# ATEM_2x8GPIOv1_1.net
KiCad netlist of a schematic drawn in EAGLE
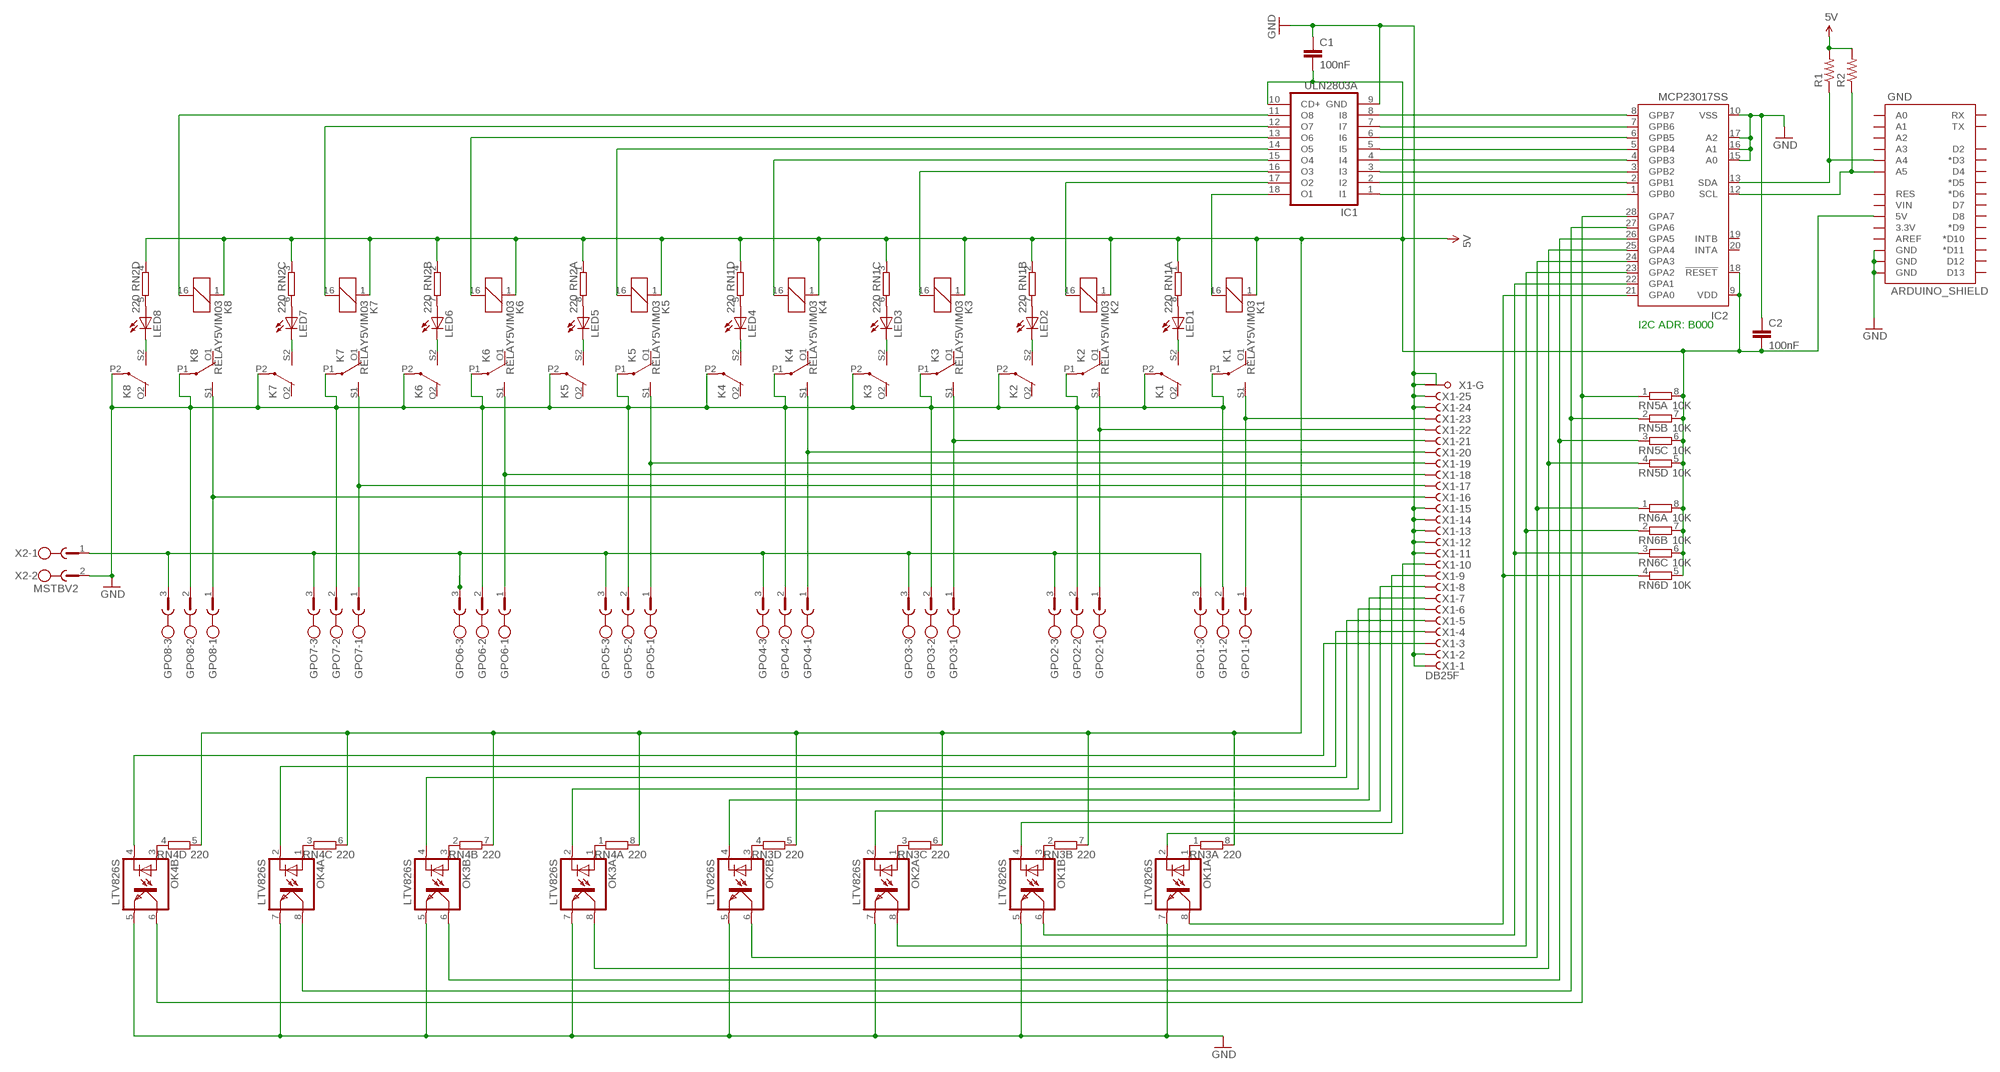
[diagram p0: schematic, sheet 1]

(export (version "E")
  (design (tool "Eeschema 10.0.6"))
  (components
    (comp (ref "C1")
      (value "100nF")
      (footprint "eagle-import:0805")
      (libsource (lib "eagle-import") (part "CAP0805"))
    )
    (comp (ref "C2")
      (value "100nF")
      (footprint "eagle-import:0603-CAP")
      (libsource (lib "eagle-import") (part "CAP0603-CAP"))
    )
    (comp (ref "GND")
      (value "ARDUINO_SHIELD")
      (footprint "eagle-import:ARDUINO_BOXSHIELD_NOHOLES")
      (libsource (lib "eagle-import") (part "ARDUINO_SHIELD"))
    )
    (comp (ref "GPO1")
      (value "CON1")
      (footprint "eagle-import:MSTBV3")
      (fields (field (name "MPN") "MSTBV 2,5/3-GF-5.08"))
      (libsource (lib "eagle-import") (part "MSTBV3"))
    )
    (comp (ref "GPO2")
      (value "CON1")
      (footprint "eagle-import:MSTBV3")
      (fields (field (name "MPN") "MSTBV 2,5/3-GF-5.08"))
      (libsource (lib "eagle-import") (part "MSTBV3"))
    )
    (comp (ref "GPO3")
      (value "CON1")
      (footprint "eagle-import:MSTBV3")
      (fields (field (name "MPN") "MSTBV 2,5/3-GF-5.08"))
      (libsource (lib "eagle-import") (part "MSTBV3"))
    )
    (comp (ref "GPO4")
      (value "CON1")
      (footprint "eagle-import:MSTBV3")
      (fields (field (name "MPN") "MSTBV 2,5/3-GF-5.08"))
      (libsource (lib "eagle-import") (part "MSTBV3"))
    )
    (comp (ref "GPO5")
      (value "CON1")
      (footprint "eagle-import:MSTBV3")
      (fields (field (name "MPN") "MSTBV 2,5/3-GF-5.08"))
      (libsource (lib "eagle-import") (part "MSTBV3"))
    )
    (comp (ref "GPO6")
      (value "CON1")
      (footprint "eagle-import:MSTBV3")
      (fields (field (name "MPN") "MSTBV 2,5/3-GF-5.08"))
      (libsource (lib "eagle-import") (part "MSTBV3"))
    )
    (comp (ref "GPO7")
      (value "CON1")
      (footprint "eagle-import:MSTBV3")
      (fields (field (name "MPN") "MSTBV 2,5/3-GF-5.08"))
      (libsource (lib "eagle-import") (part "MSTBV3"))
    )
    (comp (ref "GPO8")
      (value "GPO8")
      (footprint "eagle-import:MSTBV3")
      (fields (field (name "MPN") "MSTBV 2,5/3-GF-5.08"))
      (libsource (lib "eagle-import") (part "MSTBV3"))
    )
    (comp (ref "IC1")
      (value "ULN2803A")
      (footprint "eagle-import:SO18W")
      (libsource (lib "eagle-import") (part "ULN2803ASO18W"))
    )
    (comp (ref "IC2")
      (value "MCP23017SS")
      (footprint "eagle-import:SSOP28")
      (fields (field (name "MF") "MICROCHIP") (field (name "MPN") "MCP23017-E/SS"))
      (libsource (lib "eagle-import") (part "MCP23017SS"))
    )
    (comp (ref "K1")
      (value "RELAY5VIM03")
      (footprint "eagle-import:DS2Y")
      (libsource (lib "eagle-import") (part "RELAY5VIM03"))
    )
    (comp (ref "K2")
      (value "RELAY5VIM03")
      (footprint "eagle-import:DS2Y")
      (libsource (lib "eagle-import") (part "RELAY5VIM03"))
    )
    (comp (ref "K3")
      (value "RELAY5VIM03")
      (footprint "eagle-import:DS2Y")
      (libsource (lib "eagle-import") (part "RELAY5VIM03"))
    )
    (comp (ref "K4")
      (value "RELAY5VIM03")
      (footprint "eagle-import:DS2Y")
      (libsource (lib "eagle-import") (part "RELAY5VIM03"))
    )
    (comp (ref "K5")
      (value "RELAY5VIM03")
      (footprint "eagle-import:DS2Y")
      (libsource (lib "eagle-import") (part "RELAY5VIM03"))
    )
    (comp (ref "K6")
      (value "RELAY5VIM03")
      (footprint "eagle-import:DS2Y")
      (libsource (lib "eagle-import") (part "RELAY5VIM03"))
    )
    (comp (ref "K7")
      (value "RELAY5VIM03")
      (footprint "eagle-import:DS2Y")
      (libsource (lib "eagle-import") (part "RELAY5VIM03"))
    )
    (comp (ref "K8")
      (value "RELAY5VIM03")
      (footprint "eagle-import:DS2Y")
      (libsource (lib "eagle-import") (part "RELAY5VIM03"))
    )
    (comp (ref "LED1")
      (value "LED0603")
      (footprint "eagle-import:LED-0603")
      (libsource (lib "eagle-import") (part "LED0603"))
    )
    (comp (ref "LED2")
      (value "LED0603")
      (footprint "eagle-import:LED-0603")
      (libsource (lib "eagle-import") (part "LED0603"))
    )
    (comp (ref "LED3")
      (value "LED0603")
      (footprint "eagle-import:LED-0603")
      (libsource (lib "eagle-import") (part "LED0603"))
    )
    (comp (ref "LED4")
      (value "LED0603")
      (footprint "eagle-import:LED-0603")
      (libsource (lib "eagle-import") (part "LED0603"))
    )
    (comp (ref "LED5")
      (value "LED0603")
      (footprint "eagle-import:LED-0603")
      (libsource (lib "eagle-import") (part "LED0603"))
    )
    (comp (ref "LED6")
      (value "LED0603")
      (footprint "eagle-import:LED-0603")
      (libsource (lib "eagle-import") (part "LED0603"))
    )
    (comp (ref "LED7")
      (value "LED0603")
      (footprint "eagle-import:LED-0603")
      (libsource (lib "eagle-import") (part "LED0603"))
    )
    (comp (ref "LED8")
      (value "LED0603")
      (footprint "eagle-import:LED-0603")
      (libsource (lib "eagle-import") (part "LED0603"))
    )
    (comp (ref "OK1")
      (value "LTV826S")
      (footprint "eagle-import:DIL8-SMD")
      (libsource (lib "eagle-import") (part "LTV826S"))
    )
    (comp (ref "OK2")
      (value "LTV826S")
      (footprint "eagle-import:DIL8-SMD")
      (libsource (lib "eagle-import") (part "LTV826S"))
    )
    (comp (ref "OK3")
      (value "LTV826S")
      (footprint "eagle-import:DIL8-SMD")
      (libsource (lib "eagle-import") (part "LTV826S"))
    )
    (comp (ref "OK4")
      (value "LTV826S")
      (footprint "eagle-import:DIL8-SMD")
      (libsource (lib "eagle-import") (part "LTV826S"))
    )
    (comp (ref "R1")
      (value "RESISTOR0603-RES")
      (footprint "eagle-import:0603-RES")
      (libsource (lib "eagle-import") (part "RESISTOR0603-RES"))
    )
    (comp (ref "R2")
      (value "RESISTOR0603-RES")
      (footprint "eagle-import:0603-RES")
      (libsource (lib "eagle-import") (part "RESISTOR0603-RES"))
    )
    (comp (ref "RN1")
      (value "220")
      (footprint "eagle-import:CAY16")
      (libsource (lib "eagle-import") (part "4R-NCAY16"))
    )
    (comp (ref "RN2")
      (value "220")
      (footprint "eagle-import:CAY16")
      (libsource (lib "eagle-import") (part "4R-NCAY16"))
    )
    (comp (ref "RN3")
      (value "220")
      (footprint "eagle-import:CAY16")
      (libsource (lib "eagle-import") (part "4R-NCAY16"))
    )
    (comp (ref "RN4")
      (value "220")
      (footprint "eagle-import:CAY16")
      (libsource (lib "eagle-import") (part "4R-NCAY16"))
    )
    (comp (ref "RN5")
      (value "10K")
      (footprint "eagle-import:CAY16")
      (libsource (lib "eagle-import") (part "4R-NCAY16"))
    )
    (comp (ref "RN6")
      (value "10K")
      (footprint "eagle-import:CAY16")
      (libsource (lib "eagle-import") (part "4R-NCAY16"))
    )
    (comp (ref "X1")
      (value "DB25F")
      (footprint "eagle-import:F25HP")
      (libsource (lib "eagle-import") (part "F25HPS"))
    )
    (comp (ref "X2")
      (value "MSTBV2")
      (footprint "eagle-import:MSTBV2")
      (fields (field (name "MPN") "MSTBV 2,5/2-GF-5.08"))
      (libsource (lib "eagle-import") (part "MSTBV2"))
    )
  )
  (nets
    (net (code "1") (name "5V") (class "Default")
      (node (ref "C1") (pin "2") (pinfunction "2_2") (pintype "passive"))
      (node (ref "C2") (pin "2") (pinfunction "2_2") (pintype "passive"))
      (node (ref "GND") (pin "5V@0") (pinfunction "5V_5V@0") (pintype "bidirectional"))
      (node (ref "IC1") (pin "10") (pinfunction "CD+_10") (pintype "passive"))
      (node (ref "IC2") (pin "18") (pinfunction "~{RESET}_18") (pintype "input"))
      (node (ref "IC2") (pin "9") (pinfunction "VDD_9") (pintype "power_in"))
      (node (ref "K1") (pin "1") (pinfunction "1_1") (pintype "passive"))
      (node (ref "K2") (pin "1") (pinfunction "1_1") (pintype "passive"))
      (node (ref "K3") (pin "1") (pinfunction "1_1") (pintype "passive"))
      (node (ref "K4") (pin "1") (pinfunction "1_1") (pintype "passive"))
      (node (ref "K5") (pin "1") (pinfunction "1_1") (pintype "passive"))
      (node (ref "K6") (pin "1") (pinfunction "1_1") (pintype "passive"))
      (node (ref "K7") (pin "1") (pinfunction "1_1") (pintype "passive"))
      (node (ref "K8") (pin "1") (pinfunction "1_1") (pintype "passive"))
      (node (ref "R1") (pin "2") (pinfunction "2_2") (pintype "passive"))
      (node (ref "R2") (pin "2") (pinfunction "2_2") (pintype "passive"))
      (node (ref "RN1") (pin "1") (pinfunction "1_1") (pintype "passive"))
      (node (ref "RN1") (pin "2") (pinfunction "1_2") (pintype "passive"))
      (node (ref "RN1") (pin "3") (pinfunction "1_3") (pintype "passive"))
      (node (ref "RN1") (pin "4") (pinfunction "1_4") (pintype "passive"))
      (node (ref "RN2") (pin "1") (pinfunction "1_1") (pintype "passive"))
      (node (ref "RN2") (pin "2") (pinfunction "1_2") (pintype "passive"))
      (node (ref "RN2") (pin "3") (pinfunction "1_3") (pintype "passive"))
      (node (ref "RN2") (pin "4") (pinfunction "1_4") (pintype "passive"))
      (node (ref "RN3") (pin "5") (pinfunction "2_5") (pintype "passive"))
      (node (ref "RN3") (pin "6") (pinfunction "2_6") (pintype "passive"))
      (node (ref "RN3") (pin "7") (pinfunction "2_7") (pintype "passive"))
      (node (ref "RN3") (pin "8") (pinfunction "2_8") (pintype "passive"))
      (node (ref "RN4") (pin "5") (pinfunction "2_5") (pintype "passive"))
      (node (ref "RN4") (pin "6") (pinfunction "2_6") (pintype "passive"))
      (node (ref "RN4") (pin "7") (pinfunction "2_7") (pintype "passive"))
      (node (ref "RN4") (pin "8") (pinfunction "2_8") (pintype "passive"))
      (node (ref "RN5") (pin "5") (pinfunction "2_5") (pintype "passive"))
      (node (ref "RN5") (pin "6") (pinfunction "2_6") (pintype "passive"))
      (node (ref "RN5") (pin "7") (pinfunction "2_7") (pintype "passive"))
      (node (ref "RN5") (pin "8") (pinfunction "2_8") (pintype "passive"))
      (node (ref "RN6") (pin "5") (pinfunction "2_5") (pintype "passive"))
      (node (ref "RN6") (pin "6") (pinfunction "2_6") (pintype "passive"))
      (node (ref "RN6") (pin "7") (pinfunction "2_7") (pintype "passive"))
      (node (ref "RN6") (pin "8") (pinfunction "2_8") (pintype "passive"))
    )
    (net (code "2") (name "GND") (class "Default")
      (node (ref "C1") (pin "1") (pinfunction "1_1") (pintype "passive"))
      (node (ref "C2") (pin "1") (pinfunction "1_1") (pintype "passive"))
      (node (ref "GND") (pin "GND@0") (pinfunction "GND_GND@0") (pintype "bidirectional"))
      (node (ref "GND") (pin "GND@1") (pinfunction "GND_GND@1") (pintype "bidirectional"))
      (node (ref "GND") (pin "GND@4") (pinfunction "GND_GND@4") (pintype "bidirectional"))
      (node (ref "GPO1") (pin "2") (pinfunction "1_2") (pintype "passive"))
      (node (ref "GPO2") (pin "2") (pinfunction "1_2") (pintype "passive"))
      (node (ref "GPO3") (pin "2") (pinfunction "1_2") (pintype "passive"))
      (node (ref "GPO4") (pin "2") (pinfunction "1_2") (pintype "passive"))
      (node (ref "GPO5") (pin "2") (pinfunction "1_2") (pintype "passive"))
      (node (ref "GPO6") (pin "2") (pinfunction "1_2") (pintype "passive"))
      (node (ref "GPO7") (pin "2") (pinfunction "1_2") (pintype "passive"))
      (node (ref "GPO8") (pin "2") (pinfunction "1_2") (pintype "passive"))
      (node (ref "IC1") (pin "9") (pinfunction "GND_9") (pintype "power_in"))
      (node (ref "IC2") (pin "10") (pinfunction "VSS_10") (pintype "power_in"))
      (node (ref "IC2") (pin "15") (pinfunction "A0_15") (pintype "input"))
      (node (ref "IC2") (pin "16") (pinfunction "A1_16") (pintype "input"))
      (node (ref "IC2") (pin "17") (pinfunction "A2_17") (pintype "input"))
      (node (ref "K1") (pin "P1") (pinfunction "P_P1") (pintype "passive"))
      (node (ref "K1") (pin "P2") (pinfunction "P_P2") (pintype "passive"))
      (node (ref "K2") (pin "P1") (pinfunction "P_P1") (pintype "passive"))
      (node (ref "K2") (pin "P2") (pinfunction "P_P2") (pintype "passive"))
      (node (ref "K3") (pin "P1") (pinfunction "P_P1") (pintype "passive"))
      (node (ref "K3") (pin "P2") (pinfunction "P_P2") (pintype "passive"))
      (node (ref "K4") (pin "P1") (pinfunction "P_P1") (pintype "passive"))
      (node (ref "K4") (pin "P2") (pinfunction "P_P2") (pintype "passive"))
      (node (ref "K5") (pin "P1") (pinfunction "P_P1") (pintype "passive"))
      (node (ref "K5") (pin "P2") (pinfunction "P_P2") (pintype "passive"))
      (node (ref "K6") (pin "P1") (pinfunction "P_P1") (pintype "passive"))
      (node (ref "K6") (pin "P2") (pinfunction "P_P2") (pintype "passive"))
      (node (ref "K7") (pin "P1") (pinfunction "P_P1") (pintype "passive"))
      (node (ref "K7") (pin "P2") (pinfunction "P_P2") (pintype "passive"))
      (node (ref "K8") (pin "P1") (pinfunction "P_P1") (pintype "passive"))
      (node (ref "K8") (pin "P2") (pinfunction "P_P2") (pintype "passive"))
      (node (ref "OK1") (pin "5") (pinfunction "EMIT_5") (pintype "passive"))
      (node (ref "OK1") (pin "7") (pinfunction "EMIT_7") (pintype "passive"))
      (node (ref "OK2") (pin "5") (pinfunction "EMIT_5") (pintype "passive"))
      (node (ref "OK2") (pin "7") (pinfunction "EMIT_7") (pintype "passive"))
      (node (ref "OK3") (pin "5") (pinfunction "EMIT_5") (pintype "passive"))
      (node (ref "OK3") (pin "7") (pinfunction "EMIT_7") (pintype "passive"))
      (node (ref "OK4") (pin "5") (pinfunction "EMIT_5") (pintype "passive"))
      (node (ref "OK4") (pin "7") (pinfunction "EMIT_7") (pintype "passive"))
      (node (ref "X1") (pin "1") (pinfunction "F_1") (pintype "passive"))
      (node (ref "X1") (pin "11") (pinfunction "F_11") (pintype "passive"))
      (node (ref "X1") (pin "12") (pinfunction "F_12") (pintype "passive"))
      (node (ref "X1") (pin "13") (pinfunction "F_13") (pintype "passive"))
      (node (ref "X1") (pin "14") (pinfunction "F_14") (pintype "passive"))
      (node (ref "X1") (pin "15") (pinfunction "F_15") (pintype "passive"))
      (node (ref "X1") (pin "2") (pinfunction "F_2") (pintype "passive"))
      (node (ref "X1") (pin "24") (pinfunction "F_24") (pintype "passive"))
      (node (ref "X1") (pin "25") (pinfunction "F_25") (pintype "passive"))
      (node (ref "X1") (pin "G1") (pinfunction "G1_G1") (pintype "passive"))
      (node (ref "X1") (pin "G2") (pinfunction "G2_G2") (pintype "passive"))
      (node (ref "X2") (pin "2") (pinfunction "1_2") (pintype "passive"))
    )
    (net (code "3") (name "Net-(GPO1C-1)") (class "Default")
      (node (ref "GPO1") (pin "3") (pinfunction "1_3") (pintype "passive"))
      (node (ref "GPO2") (pin "3") (pinfunction "1_3") (pintype "passive"))
      (node (ref "GPO3") (pin "3") (pinfunction "1_3") (pintype "passive"))
      (node (ref "GPO4") (pin "3") (pinfunction "1_3") (pintype "passive"))
      (node (ref "GPO5") (pin "3") (pinfunction "1_3") (pintype "passive"))
      (node (ref "GPO6") (pin "3") (pinfunction "1_3") (pintype "passive"))
      (node (ref "GPO7") (pin "3") (pinfunction "1_3") (pintype "passive"))
      (node (ref "GPO8") (pin "3") (pinfunction "1_3") (pintype "passive"))
      (node (ref "X2") (pin "1") (pinfunction "1_1") (pintype "passive"))
    )
    (net (code "4") (name "Net-(IC1-I1)") (class "Default")
      (node (ref "IC1") (pin "1") (pinfunction "I1_1") (pintype "input"))
      (node (ref "IC2") (pin "1") (pinfunction "GPB0_1") (pintype "bidirectional"))
    )
    (net (code "5") (name "Net-(IC1-I2)") (class "Default")
      (node (ref "IC1") (pin "2") (pinfunction "I2_2") (pintype "input"))
      (node (ref "IC2") (pin "2") (pinfunction "GPB1_2") (pintype "bidirectional"))
    )
    (net (code "6") (name "Net-(IC1-I3)") (class "Default")
      (node (ref "IC1") (pin "3") (pinfunction "I3_3") (pintype "input"))
      (node (ref "IC2") (pin "3") (pinfunction "GPB2_3") (pintype "bidirectional"))
    )
    (net (code "7") (name "Net-(IC1-I4)") (class "Default")
      (node (ref "IC1") (pin "4") (pinfunction "I4_4") (pintype "input"))
      (node (ref "IC2") (pin "4") (pinfunction "GPB3_4") (pintype "bidirectional"))
    )
    (net (code "8") (name "Net-(IC1-I5)") (class "Default")
      (node (ref "IC1") (pin "5") (pinfunction "I5_5") (pintype "input"))
      (node (ref "IC2") (pin "5") (pinfunction "GPB4_5") (pintype "bidirectional"))
    )
    (net (code "9") (name "Net-(IC1-I6)") (class "Default")
      (node (ref "IC1") (pin "6") (pinfunction "I6_6") (pintype "input"))
      (node (ref "IC2") (pin "6") (pinfunction "GPB5_6") (pintype "bidirectional"))
    )
    (net (code "10") (name "Net-(IC1-I7)") (class "Default")
      (node (ref "IC1") (pin "7") (pinfunction "I7_7") (pintype "input"))
      (node (ref "IC2") (pin "7") (pinfunction "GPB6_7") (pintype "bidirectional"))
    )
    (net (code "11") (name "Net-(IC1-I8)") (class "Default")
      (node (ref "IC1") (pin "8") (pinfunction "I8_8") (pintype "input"))
      (node (ref "IC2") (pin "8") (pinfunction "GPB7_8") (pintype "bidirectional"))
    )
    (net (code "12") (name "Net-(IC1-O1)") (class "Default")
      (node (ref "IC1") (pin "18") (pinfunction "O1_18") (pintype "open_collector"))
      (node (ref "K1") (pin "16") (pinfunction "2_16") (pintype "passive"))
    )
    (net (code "13") (name "Net-(IC1-O2)") (class "Default")
      (node (ref "IC1") (pin "17") (pinfunction "O2_17") (pintype "open_collector"))
      (node (ref "K2") (pin "16") (pinfunction "2_16") (pintype "passive"))
    )
    (net (code "14") (name "Net-(IC1-O3)") (class "Default")
      (node (ref "IC1") (pin "16") (pinfunction "O3_16") (pintype "open_collector"))
      (node (ref "K3") (pin "16") (pinfunction "2_16") (pintype "passive"))
    )
    (net (code "15") (name "Net-(IC1-O4)") (class "Default")
      (node (ref "IC1") (pin "15") (pinfunction "O4_15") (pintype "open_collector"))
      (node (ref "K4") (pin "16") (pinfunction "2_16") (pintype "passive"))
    )
    (net (code "16") (name "Net-(IC1-O5)") (class "Default")
      (node (ref "IC1") (pin "14") (pinfunction "O5_14") (pintype "open_collector"))
      (node (ref "K5") (pin "16") (pinfunction "2_16") (pintype "passive"))
    )
    (net (code "17") (name "Net-(IC1-O6)") (class "Default")
      (node (ref "IC1") (pin "13") (pinfunction "O6_13") (pintype "open_collector"))
      (node (ref "K6") (pin "16") (pinfunction "2_16") (pintype "passive"))
    )
    (net (code "18") (name "Net-(IC1-O7)") (class "Default")
      (node (ref "IC1") (pin "12") (pinfunction "O7_12") (pintype "open_collector"))
      (node (ref "K7") (pin "16") (pinfunction "2_16") (pintype "passive"))
    )
    (net (code "19") (name "Net-(IC1-O8)") (class "Default")
      (node (ref "IC1") (pin "11") (pinfunction "O8_11") (pintype "open_collector"))
      (node (ref "K8") (pin "16") (pinfunction "2_16") (pintype "passive"))
    )
    (net (code "20") (name "Net-(IC2-GPA0)") (class "Default")
      (node (ref "IC2") (pin "21") (pinfunction "GPA0_21") (pintype "bidirectional"))
      (node (ref "OK1") (pin "8") (pinfunction "COL_8") (pintype "passive"))
      (node (ref "RN6") (pin "4") (pinfunction "1_4") (pintype "passive"))
    )
    (net (code "21") (name "Net-(IC2-GPA1)") (class "Default")
      (node (ref "IC2") (pin "22") (pinfunction "GPA1_22") (pintype "bidirectional"))
      (node (ref "OK1") (pin "6") (pinfunction "COL_6") (pintype "passive"))
      (node (ref "RN6") (pin "3") (pinfunction "1_3") (pintype "passive"))
    )
    (net (code "22") (name "Net-(IC2-GPA2)") (class "Default")
      (node (ref "IC2") (pin "23") (pinfunction "GPA2_23") (pintype "bidirectional"))
      (node (ref "OK2") (pin "8") (pinfunction "COL_8") (pintype "passive"))
      (node (ref "RN6") (pin "2") (pinfunction "1_2") (pintype "passive"))
    )
    (net (code "23") (name "Net-(IC2-GPA3)") (class "Default")
      (node (ref "IC2") (pin "24") (pinfunction "GPA3_24") (pintype "bidirectional"))
      (node (ref "OK2") (pin "6") (pinfunction "COL_6") (pintype "passive"))
      (node (ref "RN6") (pin "1") (pinfunction "1_1") (pintype "passive"))
    )
    (net (code "24") (name "Net-(IC2-GPA4)") (class "Default")
      (node (ref "IC2") (pin "25") (pinfunction "GPA4_25") (pintype "bidirectional"))
      (node (ref "OK3") (pin "8") (pinfunction "COL_8") (pintype "passive"))
      (node (ref "RN5") (pin "4") (pinfunction "1_4") (pintype "passive"))
    )
    (net (code "25") (name "Net-(IC2-GPA5)") (class "Default")
      (node (ref "IC2") (pin "26") (pinfunction "GPA5_26") (pintype "bidirectional"))
      (node (ref "OK3") (pin "6") (pinfunction "COL_6") (pintype "passive"))
      (node (ref "RN5") (pin "3") (pinfunction "1_3") (pintype "passive"))
    )
    (net (code "26") (name "Net-(IC2-GPA6)") (class "Default")
      (node (ref "IC2") (pin "27") (pinfunction "GPA6_27") (pintype "bidirectional"))
      (node (ref "OK4") (pin "8") (pinfunction "COL_8") (pintype "passive"))
      (node (ref "RN5") (pin "2") (pinfunction "1_2") (pintype "passive"))
    )
    (net (code "27") (name "Net-(IC2-GPA7)") (class "Default")
      (node (ref "IC2") (pin "28") (pinfunction "GPA7_28") (pintype "bidirectional"))
      (node (ref "OK4") (pin "6") (pinfunction "COL_6") (pintype "passive"))
      (node (ref "RN5") (pin "1") (pinfunction "1_1") (pintype "passive"))
    )
    (net (code "28") (name "Net-(IC2-SCL)") (class "Default")
      (node (ref "GND") (pin "A5") (pinfunction "A5_A5") (pintype "bidirectional"))
      (node (ref "IC2") (pin "12") (pinfunction "SCL_12") (pintype "input"))
      (node (ref "R2") (pin "1") (pinfunction "1_1") (pintype "passive"))
    )
    (net (code "29") (name "Net-(IC2-SDA)") (class "Default")
      (node (ref "GND") (pin "A4") (pinfunction "A4_A4") (pintype "bidirectional"))
      (node (ref "IC2") (pin "13") (pinfunction "SDA_13") (pintype "bidirectional"))
      (node (ref "R1") (pin "1") (pinfunction "1_1") (pintype "passive"))
    )
    (net (code "30") (name "Net-(K1B-S)") (class "Default")
      (node (ref "GPO1") (pin "1") (pinfunction "1_1") (pintype "passive"))
      (node (ref "K1") (pin "S1") (pinfunction "S_S1") (pintype "passive"))
      (node (ref "X1") (pin "23") (pinfunction "F_23") (pintype "passive"))
    )
    (net (code "31") (name "Net-(K1C-S)") (class "Default")
      (node (ref "K1") (pin "S2") (pinfunction "S_S2") (pintype "passive"))
      (node (ref "LED1") (pin "C") (pinfunction "C_C") (pintype "passive"))
    )
    (net (code "32") (name "Net-(K2B-S)") (class "Default")
      (node (ref "GPO2") (pin "1") (pinfunction "1_1") (pintype "passive"))
      (node (ref "K2") (pin "S1") (pinfunction "S_S1") (pintype "passive"))
      (node (ref "X1") (pin "22") (pinfunction "F_22") (pintype "passive"))
    )
    (net (code "33") (name "Net-(K2C-S)") (class "Default")
      (node (ref "K2") (pin "S2") (pinfunction "S_S2") (pintype "passive"))
      (node (ref "LED2") (pin "C") (pinfunction "C_C") (pintype "passive"))
    )
    (net (code "34") (name "Net-(K3B-S)") (class "Default")
      (node (ref "GPO3") (pin "1") (pinfunction "1_1") (pintype "passive"))
      (node (ref "K3") (pin "S1") (pinfunction "S_S1") (pintype "passive"))
      (node (ref "X1") (pin "21") (pinfunction "F_21") (pintype "passive"))
    )
    (net (code "35") (name "Net-(K3C-S)") (class "Default")
      (node (ref "K3") (pin "S2") (pinfunction "S_S2") (pintype "passive"))
      (node (ref "LED3") (pin "C") (pinfunction "C_C") (pintype "passive"))
    )
    (net (code "36") (name "Net-(K4B-S)") (class "Default")
      (node (ref "GPO4") (pin "1") (pinfunction "1_1") (pintype "passive"))
      (node (ref "K4") (pin "S1") (pinfunction "S_S1") (pintype "passive"))
      (node (ref "X1") (pin "20") (pinfunction "F_20") (pintype "passive"))
    )
    (net (code "37") (name "Net-(K4C-S)") (class "Default")
      (node (ref "K4") (pin "S2") (pinfunction "S_S2") (pintype "passive"))
      (node (ref "LED4") (pin "C") (pinfunction "C_C") (pintype "passive"))
    )
    (net (code "38") (name "Net-(K5B-S)") (class "Default")
      (node (ref "GPO5") (pin "1") (pinfunction "1_1") (pintype "passive"))
      (node (ref "K5") (pin "S1") (pinfunction "S_S1") (pintype "passive"))
      (node (ref "X1") (pin "19") (pinfunction "F_19") (pintype "passive"))
    )
    (net (code "39") (name "Net-(K5C-S)") (class "Default")
      (node (ref "K5") (pin "S2") (pinfunction "S_S2") (pintype "passive"))
      (node (ref "LED5") (pin "C") (pinfunction "C_C") (pintype "passive"))
    )
    (net (code "40") (name "Net-(K6B-S)") (class "Default")
      (node (ref "GPO6") (pin "1") (pinfunction "1_1") (pintype "passive"))
      (node (ref "K6") (pin "S1") (pinfunction "S_S1") (pintype "passive"))
      (node (ref "X1") (pin "18") (pinfunction "F_18") (pintype "passive"))
    )
    (net (code "41") (name "Net-(K6C-S)") (class "Default")
      (node (ref "K6") (pin "S2") (pinfunction "S_S2") (pintype "passive"))
      (node (ref "LED6") (pin "C") (pinfunction "C_C") (pintype "passive"))
    )
    (net (code "42") (name "Net-(K7B-S)") (class "Default")
      (node (ref "GPO7") (pin "1") (pinfunction "1_1") (pintype "passive"))
      (node (ref "K7") (pin "S1") (pinfunction "S_S1") (pintype "passive"))
      (node (ref "X1") (pin "17") (pinfunction "F_17") (pintype "passive"))
    )
    (net (code "43") (name "Net-(K7C-S)") (class "Default")
      (node (ref "K7") (pin "S2") (pinfunction "S_S2") (pintype "passive"))
      (node (ref "LED7") (pin "C") (pinfunction "C_C") (pintype "passive"))
    )
    (net (code "44") (name "Net-(K8B-S)") (class "Default")
      (node (ref "GPO8") (pin "1") (pinfunction "1_1") (pintype "passive"))
      (node (ref "K8") (pin "S1") (pinfunction "S_S1") (pintype "passive"))
      (node (ref "X1") (pin "16") (pinfunction "F_16") (pintype "passive"))
    )
    (net (code "45") (name "Net-(K8C-S)") (class "Default")
      (node (ref "K8") (pin "S2") (pinfunction "S_S2") (pintype "passive"))
      (node (ref "LED8") (pin "C") (pinfunction "C_C") (pintype "passive"))
    )
    (net (code "46") (name "Net-(OK1A-A)") (class "Default")
      (node (ref "OK1") (pin "1") (pinfunction "A_1") (pintype "passive"))
      (node (ref "RN3") (pin "1") (pinfunction "1_1") (pintype "passive"))
    )
    (net (code "47") (name "Net-(OK1A-C)") (class "Default")
      (node (ref "OK1") (pin "2") (pinfunction "C_2") (pintype "passive"))
      (node (ref "X1") (pin "10") (pinfunction "F_10") (pintype "passive"))
    )
    (net (code "48") (name "Net-(OK1B-A)") (class "Default")
      (node (ref "OK1") (pin "3") (pinfunction "A_3") (pintype "passive"))
      (node (ref "RN3") (pin "2") (pinfunction "1_2") (pintype "passive"))
    )
    (net (code "49") (name "Net-(OK1B-C)") (class "Default")
      (node (ref "OK1") (pin "4") (pinfunction "C_4") (pintype "passive"))
      (node (ref "X1") (pin "9") (pinfunction "F_9") (pintype "passive"))
    )
    (net (code "50") (name "Net-(OK2A-A)") (class "Default")
      (node (ref "OK2") (pin "1") (pinfunction "A_1") (pintype "passive"))
      (node (ref "RN3") (pin "3") (pinfunction "1_3") (pintype "passive"))
    )
    (net (code "51") (name "Net-(OK2A-C)") (class "Default")
      (node (ref "OK2") (pin "2") (pinfunction "C_2") (pintype "passive"))
      (node (ref "X1") (pin "8") (pinfunction "F_8") (pintype "passive"))
    )
    (net (code "52") (name "Net-(OK2B-A)") (class "Default")
      (node (ref "OK2") (pin "3") (pinfunction "A_3") (pintype "passive"))
      (node (ref "RN3") (pin "4") (pinfunction "1_4") (pintype "passive"))
    )
    (net (code "53") (name "Net-(OK2B-C)") (class "Default")
      (node (ref "OK2") (pin "4") (pinfunction "C_4") (pintype "passive"))
      (node (ref "X1") (pin "7") (pinfunction "F_7") (pintype "passive"))
    )
    (net (code "54") (name "Net-(OK3A-A)") (class "Default")
      (node (ref "OK3") (pin "1") (pinfunction "A_1") (pintype "passive"))
      (node (ref "RN4") (pin "1") (pinfunction "1_1") (pintype "passive"))
    )
    (net (code "55") (name "Net-(OK3A-C)") (class "Default")
      (node (ref "OK3") (pin "2") (pinfunction "C_2") (pintype "passive"))
      (node (ref "X1") (pin "6") (pinfunction "F_6") (pintype "passive"))
    )
    (net (code "56") (name "Net-(OK3B-A)") (class "Default")
      (node (ref "OK3") (pin "3") (pinfunction "A_3") (pintype "passive"))
      (node (ref "RN4") (pin "2") (pinfunction "1_2") (pintype "passive"))
    )
    (net (code "57") (name "Net-(OK3B-C)") (class "Default")
      (node (ref "OK3") (pin "4") (pinfunction "C_4") (pintype "passive"))
      (node (ref "X1") (pin "5") (pinfunction "F_5") (pintype "passive"))
    )
    (net (code "58") (name "Net-(OK4A-A)") (class "Default")
      (node (ref "OK4") (pin "1") (pinfunction "A_1") (pintype "passive"))
      (node (ref "RN4") (pin "3") (pinfunction "1_3") (pintype "passive"))
    )
    (net (code "59") (name "Net-(OK4A-C)") (class "Default")
      (node (ref "OK4") (pin "2") (pinfunction "C_2") (pintype "passive"))
      (node (ref "X1") (pin "4") (pinfunction "F_4") (pintype "passive"))
    )
    (net (code "60") (name "Net-(OK4B-A)") (class "Default")
      (node (ref "OK4") (pin "3") (pinfunction "A_3") (pintype "passive"))
      (node (ref "RN4") (pin "4") (pinfunction "1_4") (pintype "passive"))
    )
    (net (code "61") (name "Net-(OK4B-C)") (class "Default")
      (node (ref "OK4") (pin "4") (pinfunction "C_4") (pintype "passive"))
      (node (ref "X1") (pin "3") (pinfunction "F_3") (pintype "passive"))
    )
    (net (code "62") (name "Net-(RN1A-2)") (class "Default")
      (node (ref "LED1") (pin "A") (pinfunction "A_A") (pintype "passive"))
      (node (ref "RN1") (pin "8") (pinfunction "2_8") (pintype "passive"))
    )
    (net (code "63") (name "Net-(RN1B-2)") (class "Default")
      (node (ref "LED2") (pin "A") (pinfunction "A_A") (pintype "passive"))
      (node (ref "RN1") (pin "7") (pinfunction "2_7") (pintype "passive"))
    )
    (net (code "64") (name "Net-(RN1C-2)") (class "Default")
      (node (ref "LED3") (pin "A") (pinfunction "A_A") (pintype "passive"))
      (node (ref "RN1") (pin "6") (pinfunction "2_6") (pintype "passive"))
    )
    (net (code "65") (name "Net-(RN1D-2)") (class "Default")
      (node (ref "LED4") (pin "A") (pinfunction "A_A") (pintype "passive"))
      (node (ref "RN1") (pin "5") (pinfunction "2_5") (pintype "passive"))
    )
    (net (code "66") (name "Net-(RN2A-2)") (class "Default")
      (node (ref "LED5") (pin "A") (pinfunction "A_A") (pintype "passive"))
      (node (ref "RN2") (pin "8") (pinfunction "2_8") (pintype "passive"))
    )
    (net (code "67") (name "Net-(RN2B-2)") (class "Default")
      (node (ref "LED6") (pin "A") (pinfunction "A_A") (pintype "passive"))
      (node (ref "RN2") (pin "7") (pinfunction "2_7") (pintype "passive"))
    )
    (net (code "68") (name "Net-(RN2C-2)") (class "Default")
      (node (ref "LED7") (pin "A") (pinfunction "A_A") (pintype "passive"))
      (node (ref "RN2") (pin "6") (pinfunction "2_6") (pintype "passive"))
    )
    (net (code "69") (name "Net-(RN2D-2)") (class "Default")
      (node (ref "LED8") (pin "A") (pinfunction "A_A") (pintype "passive"))
      (node (ref "RN2") (pin "5") (pinfunction "2_5") (pintype "passive"))
    )
    (net (code "70") (name "unconnected-(GND-*D3-Pad3)") (class "Default")
      (node (ref "GND") (pin "3") (pinfunction "*D3_3") (pintype "bidirectional"))
    )
    (net (code "71") (name "unconnected-(GND-*D5-Pad5)") (class "Default")
      (node (ref "GND") (pin "5") (pinfunction "*D5_5") (pintype "bidirectional"))
    )
    (net (code "72") (name "unconnected-(GND-*D6-Pad6)") (class "Default")
      (node (ref "GND") (pin "6") (pinfunction "*D6_6") (pintype "bidirectional"))
    )
    (net (code "73") (name "unconnected-(GND-*D9-Pad9)") (class "Default")
      (node (ref "GND") (pin "9") (pinfunction "*D9_9") (pintype "bidirectional"))
    )
    (net (code "74") (name "unconnected-(GND-*D10-Pad10)") (class "Default")
      (node (ref "GND") (pin "10") (pinfunction "*D10_10") (pintype "bidirectional"))
    )
    (net (code "75") (name "unconnected-(GND-*D11-Pad11)") (class "Default")
      (node (ref "GND") (pin "11") (pinfunction "*D11_11") (pintype "bidirectional"))
    )
    (net (code "76") (name "unconnected-(GND-D2-Pad2)") (class "Default")
      (node (ref "GND") (pin "2") (pinfunction "D2_2") (pintype "bidirectional"))
    )
    (net (code "77") (name "unconnected-(GND-D4-Pad4)") (class "Default")
      (node (ref "GND") (pin "4") (pinfunction "D4_4") (pintype "bidirectional"))
    )
    (net (code "78") (name "unconnected-(GND-D7-Pad7)") (class "Default")
      (node (ref "GND") (pin "7") (pinfunction "D7_7") (pintype "bidirectional"))
    )
    (net (code "79") (name "unconnected-(GND-D8-Pad8)") (class "Default")
      (node (ref "GND") (pin "8") (pinfunction "D8_8") (pintype "bidirectional"))
    )
    (net (code "80") (name "unconnected-(GND-D12-Pad12)") (class "Default")
      (node (ref "GND") (pin "12") (pinfunction "D12_12") (pintype "bidirectional"))
    )
    (net (code "81") (name "unconnected-(GND-D13-Pad13)") (class "Default")
      (node (ref "GND") (pin "13") (pinfunction "D13_13") (pintype "bidirectional"))
    )
    (net (code "82") (name "unconnected-(GND-Pad3.3V)") (class "Default")
      (node (ref "GND") (pin "3.3V") (pinfunction "3.3V_3.3V") (pintype "bidirectional"))
    )
    (net (code "83") (name "unconnected-(GND-PadA0)") (class "Default")
      (node (ref "GND") (pin "A0") (pinfunction "A0_A0") (pintype "bidirectional"))
    )
    (net (code "84") (name "unconnected-(GND-PadA1)") (class "Default")
      (node (ref "GND") (pin "A1") (pinfunction "A1_A1") (pintype "bidirectional"))
    )
    (net (code "85") (name "unconnected-(GND-PadA2)") (class "Default")
      (node (ref "GND") (pin "A2") (pinfunction "A2_A2") (pintype "bidirectional"))
    )
    (net (code "86") (name "unconnected-(GND-PadA3)") (class "Default")
      (node (ref "GND") (pin "A3") (pinfunction "A3_A3") (pintype "bidirectional"))
    )
    (net (code "87") (name "unconnected-(GND-PadAREF)") (class "Default")
      (node (ref "GND") (pin "AREF") (pinfunction "AREF_AREF") (pintype "bidirectional"))
    )
    (net (code "88") (name "unconnected-(GND-PadVIN)") (class "Default")
      (node (ref "GND") (pin "VIN") (pinfunction "VIN_VIN") (pintype "bidirectional"))
    )
    (net (code "89") (name "unconnected-(GND-RES-PadRESET)") (class "Default")
      (node (ref "GND") (pin "RESET") (pinfunction "RES_RESET") (pintype "bidirectional"))
    )
    (net (code "90") (name "unconnected-(GND-RX-Pad0)") (class "Default")
      (node (ref "GND") (pin "0") (pinfunction "RX_0") (pintype "bidirectional"))
    )
    (net (code "91") (name "unconnected-(GND-TX-Pad1)") (class "Default")
      (node (ref "GND") (pin "1") (pinfunction "TX_1") (pintype "bidirectional"))
    )
    (net (code "92") (name "unconnected-(IC2-INTA-Pad20)") (class "Default")
      (node (ref "IC2") (pin "20") (pinfunction "INTA_20") (pintype "output"))
    )
    (net (code "93") (name "unconnected-(IC2-INTB-Pad19)") (class "Default")
      (node (ref "IC2") (pin "19") (pinfunction "INTB_19") (pintype "output"))
    )
    (net (code "94") (name "unconnected-(K1B-O-PadO1)") (class "Default")
      (node (ref "K1") (pin "O1") (pinfunction "O_O1") (pintype "passive"))
    )
    (net (code "95") (name "unconnected-(K1C-O-PadO2)") (class "Default")
      (node (ref "K1") (pin "O2") (pinfunction "O_O2") (pintype "passive"))
    )
    (net (code "96") (name "unconnected-(K2B-O-PadO1)") (class "Default")
      (node (ref "K2") (pin "O1") (pinfunction "O_O1") (pintype "passive"))
    )
    (net (code "97") (name "unconnected-(K2C-O-PadO2)") (class "Default")
      (node (ref "K2") (pin "O2") (pinfunction "O_O2") (pintype "passive"))
    )
    (net (code "98") (name "unconnected-(K3B-O-PadO1)") (class "Default")
      (node (ref "K3") (pin "O1") (pinfunction "O_O1") (pintype "passive"))
    )
    (net (code "99") (name "unconnected-(K3C-O-PadO2)") (class "Default")
      (node (ref "K3") (pin "O2") (pinfunction "O_O2") (pintype "passive"))
    )
    (net (code "100") (name "unconnected-(K4B-O-PadO1)") (class "Default")
      (node (ref "K4") (pin "O1") (pinfunction "O_O1") (pintype "passive"))
    )
    (net (code "101") (name "unconnected-(K4C-O-PadO2)") (class "Default")
      (node (ref "K4") (pin "O2") (pinfunction "O_O2") (pintype "passive"))
    )
    (net (code "102") (name "unconnected-(K5B-O-PadO1)") (class "Default")
      (node (ref "K5") (pin "O1") (pinfunction "O_O1") (pintype "passive"))
    )
    (net (code "103") (name "unconnected-(K5C-O-PadO2)") (class "Default")
      (node (ref "K5") (pin "O2") (pinfunction "O_O2") (pintype "passive"))
    )
    (net (code "104") (name "unconnected-(K6B-O-PadO1)") (class "Default")
      (node (ref "K6") (pin "O1") (pinfunction "O_O1") (pintype "passive"))
    )
    (net (code "105") (name "unconnected-(K6C-O-PadO2)") (class "Default")
      (node (ref "K6") (pin "O2") (pinfunction "O_O2") (pintype "passive"))
    )
    (net (code "106") (name "unconnected-(K7B-O-PadO1)") (class "Default")
      (node (ref "K7") (pin "O1") (pinfunction "O_O1") (pintype "passive"))
    )
    (net (code "107") (name "unconnected-(K7C-O-PadO2)") (class "Default")
      (node (ref "K7") (pin "O2") (pinfunction "O_O2") (pintype "passive"))
    )
    (net (code "108") (name "unconnected-(K8B-O-PadO1)") (class "Default")
      (node (ref "K8") (pin "O1") (pinfunction "O_O1") (pintype "passive"))
    )
    (net (code "109") (name "unconnected-(K8C-O-PadO2)") (class "Default")
      (node (ref "K8") (pin "O2") (pinfunction "O_O2") (pintype "passive"))
    )
  )
)
